# Power.net
KiCad netlist of a schematic drawn in Altium Designer
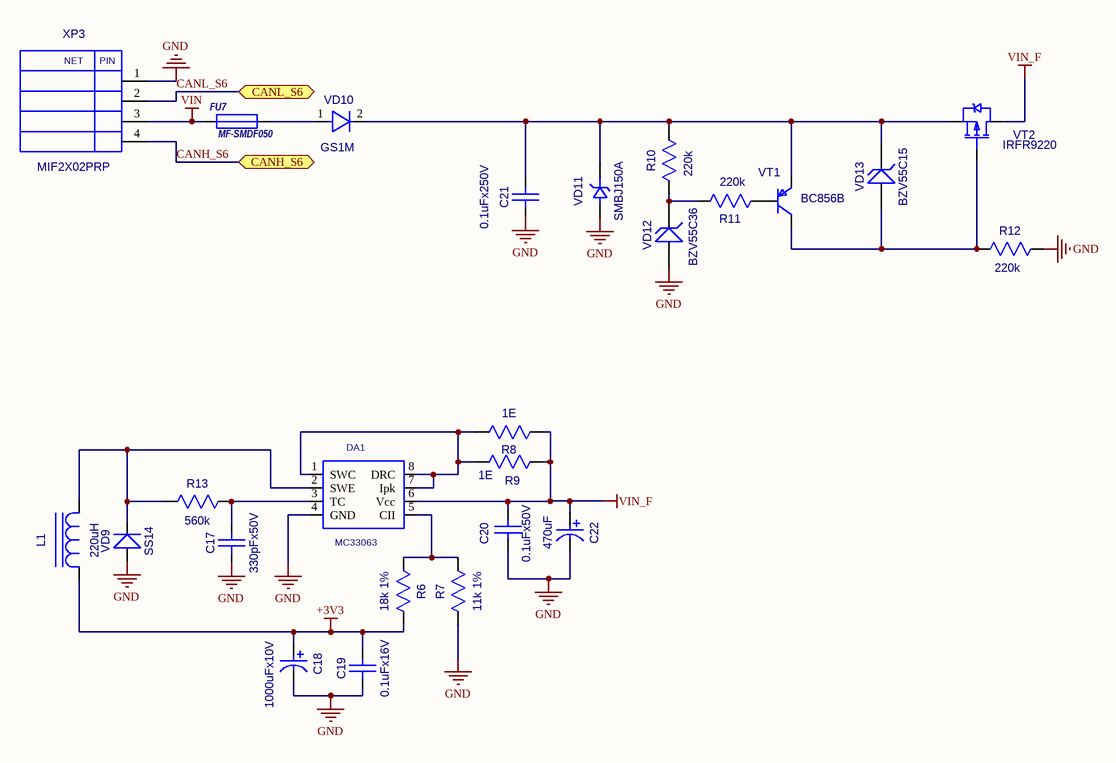
[diagram p0: Power.SchDoc]

(export (version "E")
  (design (tool "Eeschema 10.0.6"))
  (components
    (comp (ref "C17")
      (value "330pFx50V")
      (footprint "CC0603-3M")
      (description "CC0603")
      (libsource (lib "gprs_modem") (part "CC0603"))
    )
    (comp (ref "C18")
      (value "1000uFx10V")
      (footprint "CC8X3.5")
      (description "CAP0.35")
      (libsource (lib "gprs_modem") (part "CAP0.35"))
    )
    (comp (ref "C19")
      (value "0.1uFx16V")
      (footprint "CC0603-3M")
      (description "CC0603")
      (libsource (lib "gprs_modem") (part "CC0603"))
    )
    (comp (ref "C20")
      (value "0.1uFx50V")
      (footprint "CC0603-3M")
      (description "CC0603")
      (libsource (lib "gprs_modem") (part "CC0603"))
    )
    (comp (ref "C21")
      (value "0.1uFx250V")
      (footprint "CC1206-MIDI")
      (description "CC1206")
      (libsource (lib "gprs_modem") (part "CC1206"))
    )
    (comp (ref "C22")
      (value "470uF")
      (footprint "CC16X10_CAP0.5(1)(Primary)")
      (description "CAP0.5(1)")
      (libsource (lib "gprs_modem") (part "CAP0.5(1)"))
    )
    (comp (ref "DA1")
      (value "MC33063")
      (footprint "SO-8")
      (description "MC34063")
      (libsource (lib "Schetchik") (part "MC34063"))
    )
    (comp (ref "FU7")
      (value "MF-SMDF050")
      (footprint "MF-SMDF")
      (description "MF-SMDF")
      (libsource (lib "gprs_modem") (part "MF-SMDF"))
    )
    (comp (ref "L1")
      (value "220uH")
      (footprint "SDR0805")
      (description "SDR0805")
      (libsource (lib "gprs_modem") (part "SDR0805"))
    )
    (comp (ref "R6")
      (value "18k 1%")
      (footprint "RC0603-3M")
      (description "RC0603")
      (libsource (lib "gprs_modem") (part "RC0603"))
    )
    (comp (ref "R7")
      (value "11k 1%")
      (footprint "RC0603-3M")
      (description "RC0603")
      (libsource (lib "gprs_modem") (part "RC0603"))
    )
    (comp (ref "R8")
      (value "1E")
      (footprint "RC0805_IPC_NOM")
      (description "RC0805")
      (libsource (lib "gprs_modem") (part "RC0805"))
    )
    (comp (ref "R9")
      (value "1E")
      (footprint "RC0805_IPC_NOM")
      (description "RC0805")
      (libsource (lib "gprs_modem") (part "RC0805"))
    )
    (comp (ref "R10")
      (value "220k")
      (footprint "RC1206-2M")
      (description "RC1206")
      (libsource (lib "gprs_modem") (part "RC1206"))
    )
    (comp (ref "R11")
      (value "220k")
      (footprint "RC1206-2M")
      (description "RC1206")
      (libsource (lib "gprs_modem") (part "RC1206"))
    )
    (comp (ref "R12")
      (value "220k")
      (footprint "RC1206-2M")
      (description "RC1206")
      (libsource (lib "gprs_modem") (part "RC1206"))
    )
    (comp (ref "R13")
      (value "560k")
      (footprint "RC0603-3M")
      (description "RC0603")
      (libsource (lib "gprs_modem") (part "RC0603"))
    )
    (comp (ref "VD9")
      (value "SS14")
      (footprint "SMA")
      (description "Schottky Rectifier")
      (libsource (lib "gprs_modem") (part "SS14"))
    )
    (comp (ref "VD10") (value "GS1M") (footprint "SMA") (libsource (lib "Schetchik") (part "GS1M")))
    (comp (ref "VD11")
      (value "SMBJ150A")
      (footprint "SMB")
      (description "SMBJ")
      (libsource (lib "gprs_modem") (part "SMBJ"))
    )
    (comp (ref "VD12")
      (value "BZV55C36")
      (footprint "SOD-80")
      (description "Zener Voltage Regulator Diode")
      (libsource (lib "gprs_modem") (part "BZV55C12"))
    )
    (comp (ref "VD13")
      (value "BZV55C15")
      (footprint "SOD-80")
      (description "Zener Voltage Regulator Diode")
      (libsource (lib "gprs_modem") (part "BZV55C12"))
    )
    (comp (ref "VT1")
      (value "BC856B")
      (footprint "SOT-23(123)")
      (libsource (lib "Schetchik") (part "BC856B"))
    )
    (comp (ref "VT2")
      (value "IRFR9220")
      (footprint "D-PAK(TO-252AA)")
      (description "HEXFET Power MOSFET")
      (libsource (lib "gprs_modem") (part "IRFR9220"))
    )
    (comp (ref "XP3")
      (value "MIF2X02PRP")
      (footprint "MIF2X02PRP")
      (libsource (lib "Schetchik") (part "MIF2X02PRP"))
    )
  )
  (nets
    (net (code "1") (name "+3V3") (class "Default")
      (node (ref "C18") (pin "1") (pintype "passive"))
      (node (ref "C19") (pin "2") (pinfunction "B_2") (pintype "passive"))
      (node (ref "L1") (pin "1") (pinfunction "C_1") (pintype "passive"))
      (node (ref "R6") (pin "2") (pinfunction "B_2") (pintype "passive"))
    )
    (net (code "2") (name "/CANH_S6") (class "Default")
      (node (ref "XP3") (pin "4") (pinfunction "4_4") (pintype "passive"))
    )
    (net (code "3") (name "/CANL_S6") (class "Default")
      (node (ref "XP3") (pin "2") (pinfunction "2_2") (pintype "passive"))
    )
    (net (code "4") (name "GND") (class "Default")
      (node (ref "C17") (pin "1") (pinfunction "A_1") (pintype "passive"))
      (node (ref "C18") (pin "2") (pintype "passive"))
      (node (ref "C19") (pin "1") (pinfunction "A_1") (pintype "passive"))
      (node (ref "C20") (pin "2") (pinfunction "B_2") (pintype "passive"))
      (node (ref "C21") (pin "1") (pinfunction "A_1") (pintype "passive"))
      (node (ref "C22") (pin "1") (pintype "passive"))
      (node (ref "DA1") (pin "4") (pinfunction "GND_4") (pintype "passive"))
      (node (ref "R12") (pin "2") (pinfunction "B_2") (pintype "passive"))
      (node (ref "R7") (pin "1") (pinfunction "A_1") (pintype "passive"))
      (node (ref "VD11") (pin "1") (pinfunction "A_1") (pintype "passive"))
      (node (ref "VD12") (pin "1") (pinfunction "A_1") (pintype "passive"))
      (node (ref "VD9") (pin "1") (pinfunction "A_1") (pintype "passive"))
      (node (ref "XP3") (pin "1") (pinfunction "1_1") (pintype "passive"))
    )
    (net (code "5") (name "Net-(C17-B)") (class "Default")
      (node (ref "C17") (pin "2") (pinfunction "B_2") (pintype "passive"))
      (node (ref "DA1") (pin "3") (pinfunction "TC_3") (pintype "passive"))
      (node (ref "R13") (pin "2") (pinfunction "B_2") (pintype "passive"))
    )
    (net (code "6") (name "Net-(C21-B)") (class "Default")
      (node (ref "C21") (pin "2") (pinfunction "B_2") (pintype "passive"))
      (node (ref "R10") (pin "2") (pinfunction "B_2") (pintype "passive"))
      (node (ref "VD10") (pin "2") (pinfunction "K_2") (pintype "passive"))
      (node (ref "VD11") (pin "2") (pinfunction "K_2") (pintype "passive"))
      (node (ref "VD13") (pin "2") (pintype "passive"))
      (node (ref "VT1") (pin "2") (pinfunction "E_2") (pintype "passive"))
      (node (ref "VT2") (pin "2") (pinfunction "S_2") (pintype "passive"))
    )
    (net (code "7") (name "Net-(DA1-CII)") (class "Default")
      (node (ref "DA1") (pin "5") (pinfunction "CII_5") (pintype "passive"))
      (node (ref "R6") (pin "1") (pinfunction "A_1") (pintype "passive"))
      (node (ref "R7") (pin "2") (pinfunction "B_2") (pintype "passive"))
    )
    (net (code "8") (name "Net-(DA1-DRC)") (class "Default")
      (node (ref "DA1") (pin "1") (pinfunction "SWC_1") (pintype "passive"))
      (node (ref "DA1") (pin "7") (pinfunction "Ipk_7") (pintype "passive"))
      (node (ref "DA1") (pin "8") (pinfunction "DRC_8") (pintype "passive"))
      (node (ref "R8") (pin "2") (pinfunction "B_2") (pintype "passive"))
      (node (ref "R9") (pin "2") (pinfunction "B_2") (pintype "passive"))
    )
    (net (code "9") (name "Net-(DA1-SWE)") (class "Default")
      (node (ref "DA1") (pin "2") (pinfunction "SWE_2") (pintype "passive"))
      (node (ref "L1") (pin "2") (pinfunction "A_2") (pintype "passive"))
      (node (ref "R13") (pin "1") (pinfunction "A_1") (pintype "passive"))
      (node (ref "VD9") (pin "2") (pinfunction "K_2") (pintype "passive"))
    )
    (net (code "10") (name "Net-(R10-A)") (class "Default")
      (node (ref "R10") (pin "1") (pinfunction "A_1") (pintype "passive"))
      (node (ref "R11") (pin "2") (pinfunction "B_2") (pintype "passive"))
      (node (ref "VD12") (pin "2") (pintype "passive"))
    )
    (net (code "11") (name "Net-(R11-A)") (class "Default")
      (node (ref "R11") (pin "1") (pinfunction "A_1") (pintype "passive"))
      (node (ref "VT1") (pin "1") (pinfunction "B_1") (pintype "passive"))
    )
    (net (code "12") (name "Net-(R12-A)") (class "Default")
      (node (ref "R12") (pin "1") (pinfunction "A_1") (pintype "passive"))
      (node (ref "VD13") (pin "1") (pinfunction "A_1") (pintype "passive"))
      (node (ref "VT1") (pin "3") (pinfunction "C_3") (pintype "passive"))
      (node (ref "VT2") (pin "1") (pinfunction "G_1") (pintype "passive"))
    )
    (net (code "13") (name "Net-(VD10-A)") (class "Default")
      (node (ref "FU7") (pin "2") (pintype "passive"))
      (node (ref "VD10") (pin "1") (pinfunction "A_1") (pintype "passive"))
    )
    (net (code "14") (name "VIN") (class "Default")
      (node (ref "FU7") (pin "1") (pintype "passive"))
      (node (ref "XP3") (pin "3") (pinfunction "3_3") (pintype "passive"))
    )
    (net (code "15") (name "VIN_F") (class "Default")
      (node (ref "C20") (pin "1") (pinfunction "A_1") (pintype "passive"))
      (node (ref "C22") (pin "2") (pintype "passive"))
      (node (ref "DA1") (pin "6") (pinfunction "Vcc_6") (pintype "passive"))
      (node (ref "R8") (pin "1") (pinfunction "A_1") (pintype "passive"))
      (node (ref "R9") (pin "1") (pinfunction "A_1") (pintype "passive"))
      (node (ref "VT2") (pin "3") (pinfunction "D_3") (pintype "passive"))
    )
  )
)
